# adsr-schematic.net
KiCad netlist of a schematic drawn in EAGLE
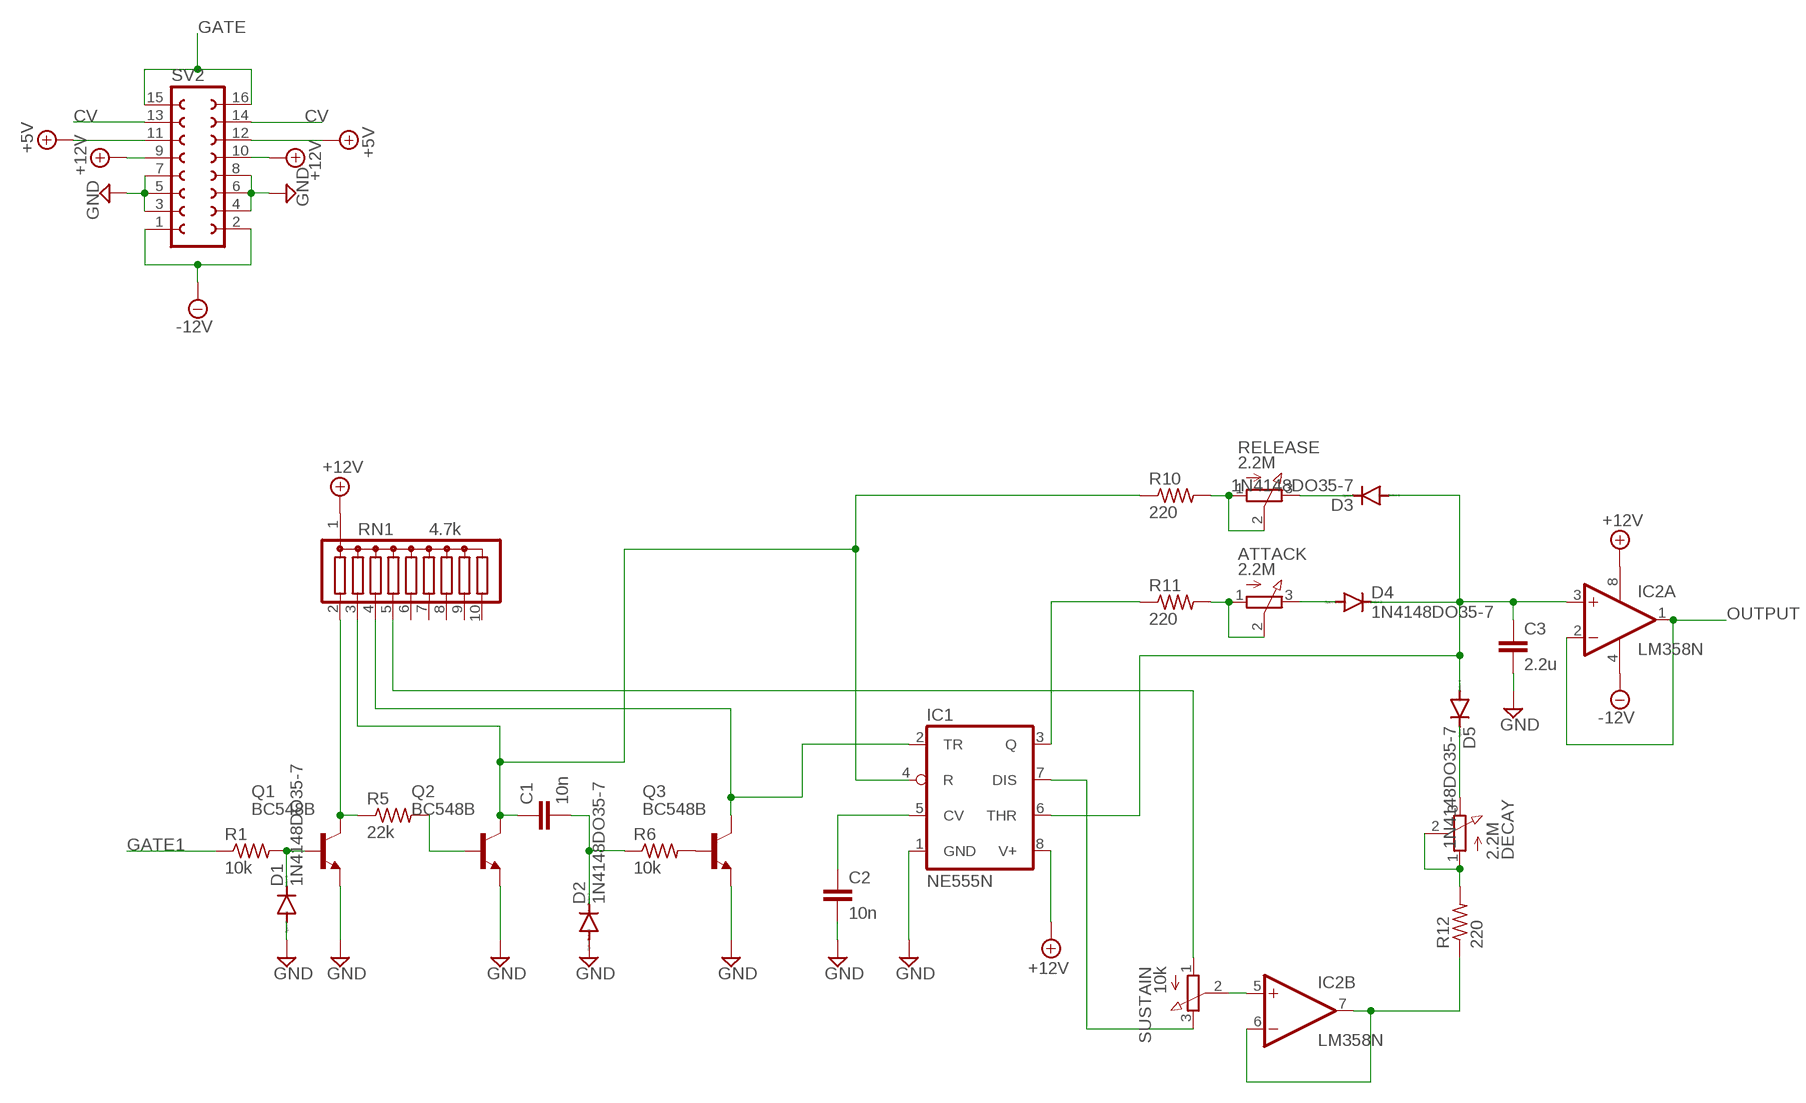
[diagram p0: schematic, sheet 1]

(export (version "E")
  (design (tool "Eeschema 10.0.6"))
  (components
    (comp (ref "ATTACK")
      (value "2.2M")
      (footprint "eagle-import:3RP_1610N")
      (libsource (lib "eagle-import") (part "3RP/1610N"))
    )
    (comp (ref "C1")
      (value "10n")
      (footprint "eagle-import:C2.5-4")
      (libsource (lib "eagle-import") (part "C2.5/4"))
    )
    (comp (ref "C2")
      (value "10n")
      (footprint "eagle-import:C2.5-4")
      (libsource (lib "eagle-import") (part "C2.5/4"))
    )
    (comp (ref "C3")
      (value "2.2u")
      (footprint "eagle-import:C2.5-4")
      (libsource (lib "eagle-import") (part "C2.5/4"))
    )
    (comp (ref "D1")
      (value "1N4148DO35-7")
      (footprint "eagle-import:DO35-7")
      (libsource (lib "eagle-import") (part "1N4148DO35-7"))
    )
    (comp (ref "D2")
      (value "1N4148DO35-7")
      (footprint "eagle-import:DO35-7")
      (libsource (lib "eagle-import") (part "1N4148DO35-7"))
    )
    (comp (ref "D3")
      (value "1N4148DO35-7")
      (footprint "eagle-import:DO35-7")
      (libsource (lib "eagle-import") (part "1N4148DO35-7"))
    )
    (comp (ref "D4")
      (value "1N4148DO35-7")
      (footprint "eagle-import:DO35-7")
      (libsource (lib "eagle-import") (part "1N4148DO35-7"))
    )
    (comp (ref "D5")
      (value "1N4148DO35-7")
      (footprint "eagle-import:DO35-7")
      (libsource (lib "eagle-import") (part "1N4148DO35-7"))
    )
    (comp (ref "DECAY")
      (value "2.2M")
      (footprint "eagle-import:3RP_1610N")
      (libsource (lib "eagle-import") (part "3RP/1610N"))
    )
    (comp (ref "IC1")
      (value "NE555N")
      (footprint "eagle-import:DIL08")
      (libsource (lib "eagle-import") (part "555NNE"))
    )
    (comp (ref "IC2")
      (value "LM358N")
      (footprint "eagle-import:DIL08")
      (libsource (lib "eagle-import") (part "LM358N"))
    )
    (comp (ref "Q1")
      (value "BC548B")
      (footprint "eagle-import:TO92-EBC")
      (libsource (lib "eagle-import") (part "BC548B"))
    )
    (comp (ref "Q2")
      (value "BC548B")
      (footprint "eagle-import:TO92-EBC")
      (libsource (lib "eagle-import") (part "BC548B"))
    )
    (comp (ref "Q3")
      (value "BC548B")
      (footprint "eagle-import:TO92-EBC")
      (libsource (lib "eagle-import") (part "BC548B"))
    )
    (comp (ref "R1")
      (value "10k")
      (footprint "eagle-import:0204_5")
      (libsource (lib "eagle-import") (part "R-US_0204/5"))
    )
    (comp (ref "R5")
      (value "22k")
      (footprint "eagle-import:0204_5")
      (libsource (lib "eagle-import") (part "R-US_0204/5"))
    )
    (comp (ref "R6")
      (value "10k")
      (footprint "eagle-import:0204_5")
      (libsource (lib "eagle-import") (part "R-US_0204/5"))
    )
    (comp (ref "R10")
      (value "220")
      (footprint "eagle-import:0204_5")
      (libsource (lib "eagle-import") (part "R-US_0204/5"))
    )
    (comp (ref "R11")
      (value "220")
      (footprint "eagle-import:0204_5")
      (libsource (lib "eagle-import") (part "R-US_0204/5"))
    )
    (comp (ref "R12")
      (value "220")
      (footprint "eagle-import:0204_5")
      (libsource (lib "eagle-import") (part "R-US_0204/5"))
    )
    (comp (ref "RELEASE")
      (value "2.2M")
      (footprint "eagle-import:3RP_1610N")
      (libsource (lib "eagle-import") (part "3RP/1610N"))
    )
    (comp (ref "RN1")
      (value "4.7k")
      (footprint "eagle-import:SIL10")
      (libsource (lib "eagle-import") (part "G09R"))
    )
    (comp (ref "SUSTAIN")
      (value "10k")
      (footprint "eagle-import:3RP_1610N")
      (libsource (lib "eagle-import") (part "3RP/1610N"))
    )
    (comp (ref "SV2")
      (value "FE08-2W")
      (footprint "eagle-import:FE08-2W")
      (libsource (lib "eagle-import") (part "FE08-2W"))
    )
  )
  (nets
    (net (code "1") (name "+5V") (class "Default")
      (node (ref "SV2") (pin "11") (pinfunction "11_11") (pintype "passive"))
      (node (ref "SV2") (pin "12") (pinfunction "12_12") (pintype "passive"))
    )
    (net (code "2") (name "+12V") (class "Default")
      (node (ref "IC1") (pin "8") (pinfunction "V+_8") (pintype "power_in"))
      (node (ref "IC2") (pin "8") (pinfunction "V+_8") (pintype "power_in"))
      (node (ref "RN1") (pin "1") (pinfunction "1_1") (pintype "passive"))
      (node (ref "SV2") (pin "10") (pinfunction "10_10") (pintype "passive"))
      (node (ref "SV2") (pin "9") (pinfunction "9_9") (pintype "passive"))
    )
    (net (code "3") (name "-12V") (class "Default")
      (node (ref "IC2") (pin "4") (pinfunction "V-_4") (pintype "power_in"))
      (node (ref "SV2") (pin "1") (pinfunction "1_1") (pintype "passive"))
      (node (ref "SV2") (pin "2") (pinfunction "2_2") (pintype "passive"))
    )
    (net (code "4") (name "/CV") (class "Default")
      (node (ref "SV2") (pin "13") (pinfunction "13_13") (pintype "passive"))
      (node (ref "SV2") (pin "14") (pinfunction "14_14") (pintype "passive"))
    )
    (net (code "5") (name "/GATE") (class "Default")
      (node (ref "SV2") (pin "15") (pinfunction "15_15") (pintype "passive"))
      (node (ref "SV2") (pin "16") (pinfunction "16_16") (pintype "passive"))
    )
    (net (code "6") (name "/GATE1") (class "Default")
      (node (ref "R1") (pin "1") (pinfunction "1_1") (pintype "passive"))
    )
    (net (code "7") (name "/OUTPUT") (class "Default")
      (node (ref "IC2") (pin "1") (pinfunction "OUT_1") (pintype "output"))
      (node (ref "IC2") (pin "2") (pinfunction "-IN_2") (pintype "input"))
    )
    (net (code "8") (name "GND") (class "Default")
      (node (ref "C2") (pin "2") (pinfunction "2_2") (pintype "passive"))
      (node (ref "C3") (pin "2") (pinfunction "2_2") (pintype "passive"))
      (node (ref "D1") (pin "A") (pinfunction "A_A") (pintype "passive"))
      (node (ref "D2") (pin "A") (pinfunction "A_A") (pintype "passive"))
      (node (ref "IC1") (pin "1") (pinfunction "GND_1") (pintype "power_in"))
      (node (ref "Q1") (pin "E") (pinfunction "E_E") (pintype "passive"))
      (node (ref "Q2") (pin "E") (pinfunction "E_E") (pintype "passive"))
      (node (ref "Q3") (pin "E") (pinfunction "E_E") (pintype "passive"))
      (node (ref "SV2") (pin "3") (pinfunction "3_3") (pintype "passive"))
      (node (ref "SV2") (pin "4") (pinfunction "4_4") (pintype "passive"))
      (node (ref "SV2") (pin "5") (pinfunction "5_5") (pintype "passive"))
      (node (ref "SV2") (pin "6") (pinfunction "6_6") (pintype "passive"))
      (node (ref "SV2") (pin "7") (pinfunction "7_7") (pintype "passive"))
      (node (ref "SV2") (pin "8") (pinfunction "8_8") (pintype "passive"))
    )
    (net (code "9") (name "Net-(ATTACK-A)") (class "Default")
      (node (ref "ATTACK") (pin "1") (pinfunction "A_1") (pintype "passive"))
      (node (ref "ATTACK") (pin "2") (pinfunction "S_2") (pintype "passive"))
      (node (ref "R11") (pin "2") (pinfunction "2_2") (pintype "passive"))
    )
    (net (code "10") (name "Net-(ATTACK-E)") (class "Default")
      (node (ref "ATTACK") (pin "3") (pinfunction "E_3") (pintype "passive"))
      (node (ref "D4") (pin "A") (pinfunction "A_A") (pintype "passive"))
    )
    (net (code "11") (name "Net-(C1-Pad2)") (class "Default")
      (node (ref "C1") (pin "2") (pinfunction "2_2") (pintype "passive"))
      (node (ref "D2") (pin "C") (pinfunction "C_C") (pintype "passive"))
      (node (ref "R6") (pin "1") (pinfunction "1_1") (pintype "passive"))
    )
    (net (code "12") (name "Net-(D1-PadC)") (class "Default")
      (node (ref "D1") (pin "C") (pinfunction "C_C") (pintype "passive"))
      (node (ref "Q1") (pin "B") (pinfunction "B_B") (pintype "passive"))
      (node (ref "R1") (pin "2") (pinfunction "2_2") (pintype "passive"))
    )
    (net (code "13") (name "Net-(DECAY-A)") (class "Default")
      (node (ref "DECAY") (pin "1") (pinfunction "A_1") (pintype "passive"))
      (node (ref "DECAY") (pin "2") (pinfunction "S_2") (pintype "passive"))
      (node (ref "R12") (pin "2") (pinfunction "2_2") (pintype "passive"))
    )
    (net (code "14") (name "Net-(DECAY-E)") (class "Default")
      (node (ref "D5") (pin "C") (pinfunction "C_C") (pintype "passive"))
      (node (ref "DECAY") (pin "3") (pinfunction "E_3") (pintype "passive"))
    )
    (net (code "15") (name "Net-(IC1-CV)") (class "Default")
      (node (ref "C2") (pin "1") (pinfunction "1_1") (pintype "passive"))
      (node (ref "IC1") (pin "5") (pinfunction "CV_5") (pintype "input"))
    )
    (net (code "16") (name "Net-(IC1-DIS)") (class "Default")
      (node (ref "IC1") (pin "7") (pinfunction "DIS_7") (pintype "input"))
      (node (ref "SUSTAIN") (pin "3") (pinfunction "E_3") (pintype "passive"))
    )
    (net (code "17") (name "Net-(IC1-Q)") (class "Default")
      (node (ref "IC1") (pin "3") (pinfunction "Q_3") (pintype "output"))
      (node (ref "R11") (pin "1") (pinfunction "1_1") (pintype "passive"))
    )
    (net (code "18") (name "Net-(IC1-R)") (class "Default")
      (node (ref "C1") (pin "1") (pinfunction "1_1") (pintype "passive"))
      (node (ref "IC1") (pin "4") (pinfunction "R_4") (pintype "input"))
      (node (ref "Q2") (pin "C") (pinfunction "C_C") (pintype "passive"))
      (node (ref "R10") (pin "1") (pinfunction "1_1") (pintype "passive"))
      (node (ref "RN1") (pin "3") (pinfunction "3_3") (pintype "passive"))
    )
    (net (code "19") (name "Net-(IC1-THR)") (class "Default")
      (node (ref "C3") (pin "1") (pinfunction "1_1") (pintype "passive"))
      (node (ref "D3") (pin "A") (pinfunction "A_A") (pintype "passive"))
      (node (ref "D4") (pin "C") (pinfunction "C_C") (pintype "passive"))
      (node (ref "D5") (pin "A") (pinfunction "A_A") (pintype "passive"))
      (node (ref "IC1") (pin "6") (pinfunction "THR_6") (pintype "input"))
      (node (ref "IC2") (pin "3") (pinfunction "+IN_3") (pintype "input"))
    )
    (net (code "20") (name "Net-(IC1-TR)") (class "Default")
      (node (ref "IC1") (pin "2") (pinfunction "TR_2") (pintype "input"))
      (node (ref "Q3") (pin "C") (pinfunction "C_C") (pintype "passive"))
      (node (ref "RN1") (pin "4") (pinfunction "4_4") (pintype "passive"))
    )
    (net (code "21") (name "Net-(IC2B-+IN)") (class "Default")
      (node (ref "IC2") (pin "5") (pinfunction "+IN_5") (pintype "input"))
      (node (ref "SUSTAIN") (pin "2") (pinfunction "S_2") (pintype "passive"))
    )
    (net (code "22") (name "Net-(IC2B--IN)") (class "Default")
      (node (ref "IC2") (pin "6") (pinfunction "-IN_6") (pintype "input"))
      (node (ref "IC2") (pin "7") (pinfunction "OUT_7") (pintype "output"))
      (node (ref "R12") (pin "1") (pinfunction "1_1") (pintype "passive"))
    )
    (net (code "23") (name "Net-(Q1-PadC)") (class "Default")
      (node (ref "Q1") (pin "C") (pinfunction "C_C") (pintype "passive"))
      (node (ref "R5") (pin "1") (pinfunction "1_1") (pintype "passive"))
      (node (ref "RN1") (pin "2") (pinfunction "2_2") (pintype "passive"))
    )
    (net (code "24") (name "Net-(Q2-PadB)") (class "Default")
      (node (ref "Q2") (pin "B") (pinfunction "B_B") (pintype "passive"))
      (node (ref "R5") (pin "2") (pinfunction "2_2") (pintype "passive"))
    )
    (net (code "25") (name "Net-(Q3-PadB)") (class "Default")
      (node (ref "Q3") (pin "B") (pinfunction "B_B") (pintype "passive"))
      (node (ref "R6") (pin "2") (pinfunction "2_2") (pintype "passive"))
    )
    (net (code "26") (name "Net-(RELEASE-A)") (class "Default")
      (node (ref "R10") (pin "2") (pinfunction "2_2") (pintype "passive"))
      (node (ref "RELEASE") (pin "1") (pinfunction "A_1") (pintype "passive"))
      (node (ref "RELEASE") (pin "2") (pinfunction "S_2") (pintype "passive"))
    )
    (net (code "27") (name "Net-(RELEASE-E)") (class "Default")
      (node (ref "D3") (pin "C") (pinfunction "C_C") (pintype "passive"))
      (node (ref "RELEASE") (pin "3") (pinfunction "E_3") (pintype "passive"))
    )
    (net (code "28") (name "Net-(SUSTAIN-A)") (class "Default")
      (node (ref "RN1") (pin "5") (pinfunction "5_5") (pintype "passive"))
      (node (ref "SUSTAIN") (pin "1") (pinfunction "A_1") (pintype "passive"))
    )
    (net (code "29") (name "unconnected-(RN1-Pad6)") (class "Default")
      (node (ref "RN1") (pin "6") (pinfunction "6_6") (pintype "passive"))
    )
    (net (code "30") (name "unconnected-(RN1-Pad7)") (class "Default")
      (node (ref "RN1") (pin "7") (pinfunction "7_7") (pintype "passive"))
    )
    (net (code "31") (name "unconnected-(RN1-Pad8)") (class "Default")
      (node (ref "RN1") (pin "8") (pinfunction "8_8") (pintype "passive"))
    )
    (net (code "32") (name "unconnected-(RN1-Pad9)") (class "Default")
      (node (ref "RN1") (pin "9") (pinfunction "9_9") (pintype "passive"))
    )
    (net (code "33") (name "unconnected-(RN1-Pad10)") (class "Default")
      (node (ref "RN1") (pin "10") (pinfunction "10_10") (pintype "passive"))
    )
  )
)
